# BYOB-BoosterPack-Template.net
KiCad netlist of a schematic drawn in EAGLE
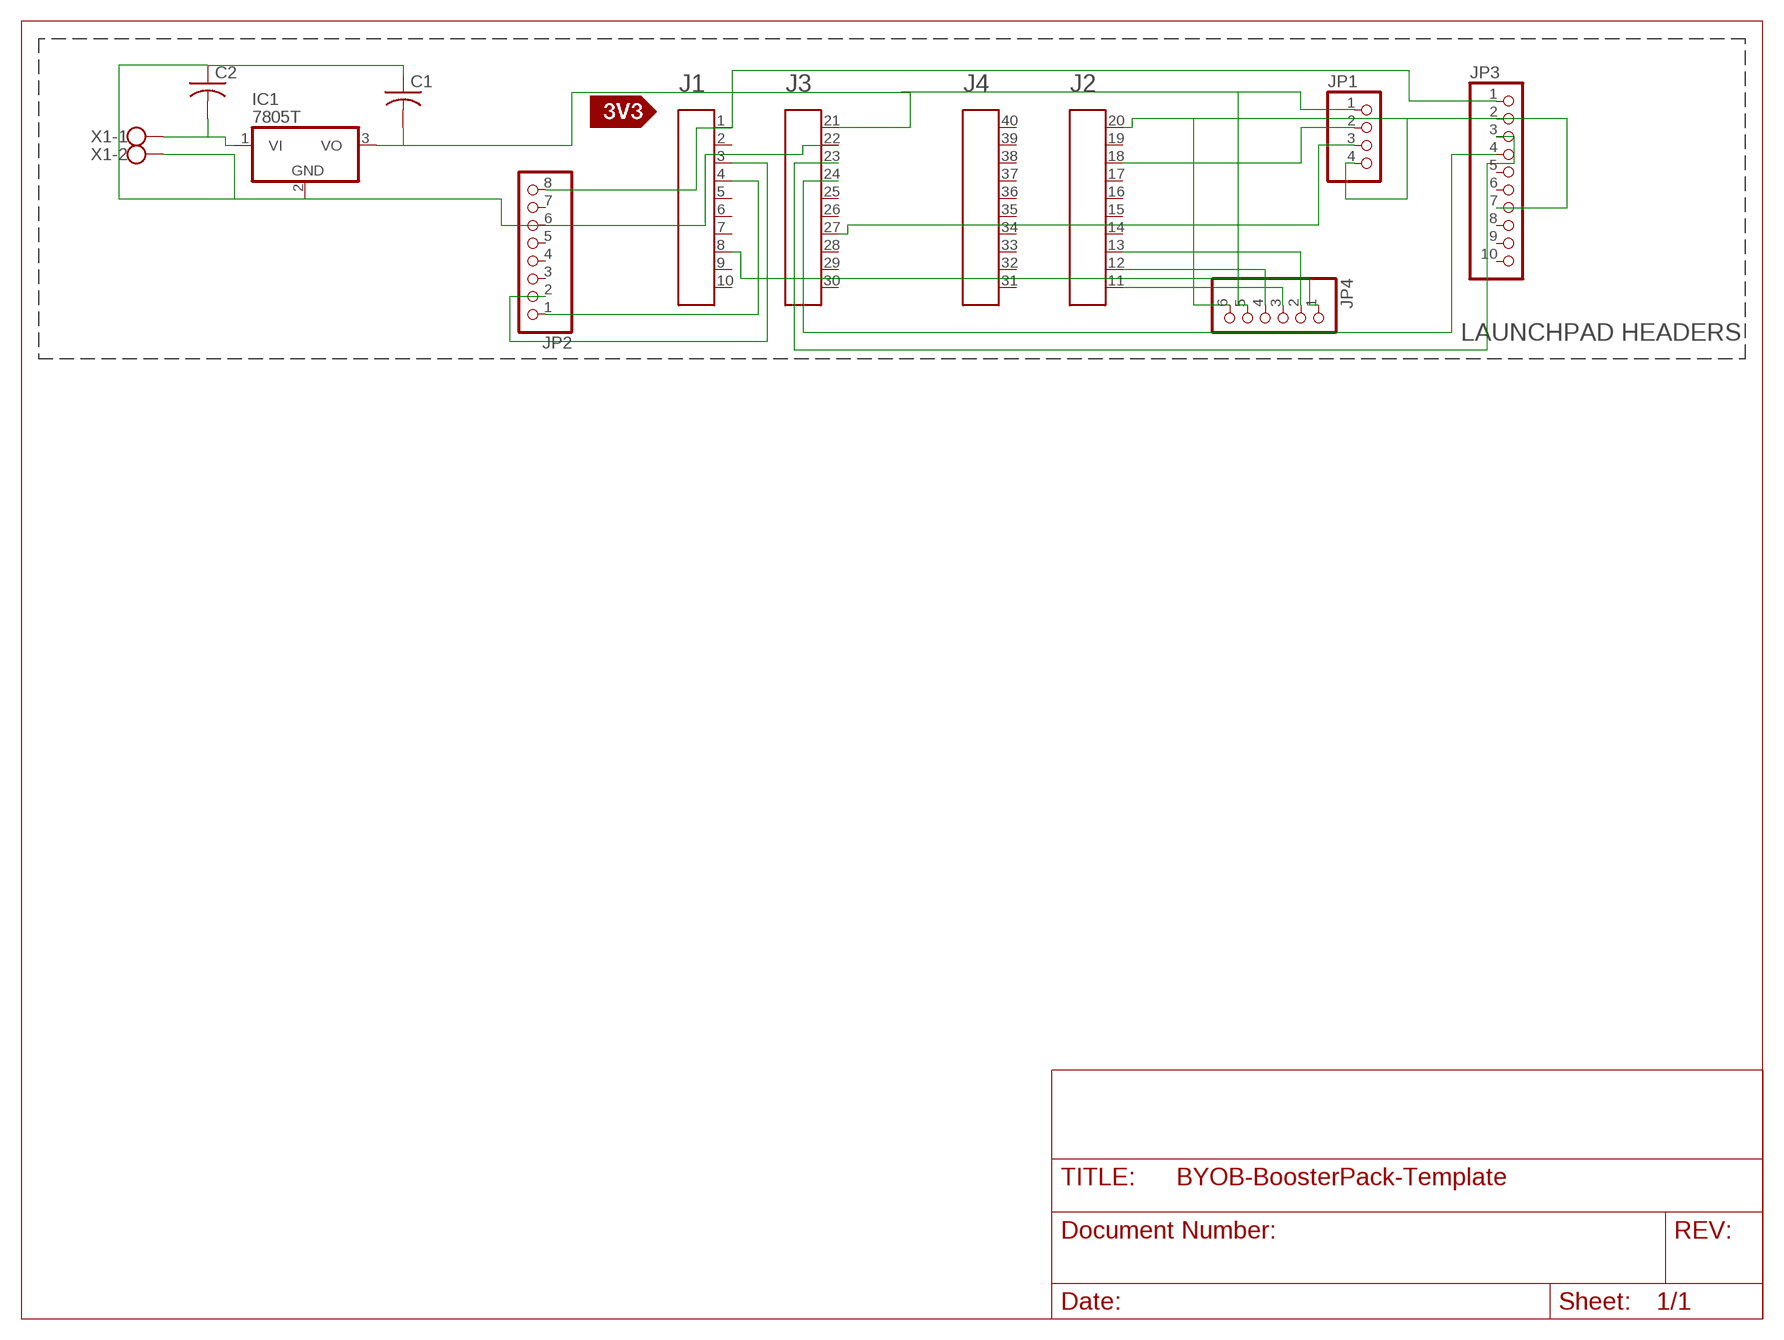
[diagram p0: schematic, sheet 1]

(export (version "E")
  (design (tool "Eeschema 10.0.6"))
  (components
    (comp (ref "A1")
      (value "HEADER4X10-BOOSTERPACK")
      (footprint "eagle-import:4X10-BOOSTERPACK")
      (libsource (lib "eagle-import") (part "HEADER4X10-BOOSTERPACK"))
    )
    (comp (ref "C1")
      (value "C-US025-025X050")
      (footprint "eagle-import:C025-025X050")
      (libsource (lib "eagle-import") (part "C-US025-025X050"))
    )
    (comp (ref "C2")
      (value "C-US025-025X050")
      (footprint "eagle-import:C025-025X050")
      (libsource (lib "eagle-import") (part "C-US025-025X050"))
    )
    (comp (ref "IC1")
      (value "7805T")
      (footprint "eagle-import:TO220H")
      (libsource (lib "eagle-import") (part "78T05"))
    )
    (comp (ref "JP1")
      (value "PINHD-1X4")
      (footprint "eagle-import:1X04")
      (libsource (lib "eagle-import") (part "PINHD-1X4"))
    )
    (comp (ref "JP2")
      (value "PINHD-1X8")
      (footprint "eagle-import:1X08")
      (libsource (lib "eagle-import") (part "PINHD-1X8"))
    )
    (comp (ref "JP3")
      (value "PINHD-1X10")
      (footprint "eagle-import:1X10")
      (libsource (lib "eagle-import") (part "PINHD-1X10"))
    )
    (comp (ref "JP4")
      (value "PINHD-1X6")
      (footprint "eagle-import:1X06")
      (libsource (lib "eagle-import") (part "PINHD-1X6"))
    )
    (comp (ref "U$3")
      (value "SILK_3V3_TAG")
      (footprint "eagle-import:SILK_3V3_TAG")
      (libsource (lib "eagle-import") (part "SILK_3V3_TAG"))
    )
    (comp (ref "X1")
      (value "W237-102")
      (footprint "eagle-import:W237-102")
      (fields (field (name "MPN") "237-102"))
      (libsource (lib "eagle-import") (part "W237-102"))
    )
  )
  (nets
    (net (code "1") (name "/GND") (class "Default")
      (node (ref "A1") (pin "20") (pinfunction "P$20_20") (pintype "bidirectional"))
      (node (ref "A1") (pin "22") (pinfunction "P$22_22") (pintype "bidirectional"))
      (node (ref "C1") (pin "1") (pinfunction "1_1") (pintype "passive"))
      (node (ref "C2") (pin "1") (pinfunction "1_1") (pintype "passive"))
      (node (ref "IC1") (pin "2") (pinfunction "GND_2") (pintype "passive"))
      (node (ref "JP1") (pin "4") (pinfunction "4_4") (pintype "passive"))
      (node (ref "JP2") (pin "6") (pinfunction "6_6") (pintype "passive"))
      (node (ref "JP3") (pin "2") (pinfunction "2_2") (pintype "passive"))
      (node (ref "JP3") (pin "7") (pinfunction "7_7") (pintype "passive"))
      (node (ref "JP4") (pin "6") (pinfunction "6_6") (pintype "passive"))
      (node (ref "X1") (pin "2") (pinfunction "KL_2") (pintype "passive"))
    )
    (net (code "2") (name "Net-(A1-P$1)") (class "Default")
      (node (ref "A1") (pin "1") (pinfunction "P$1_1") (pintype "bidirectional"))
      (node (ref "JP2") (pin "8") (pinfunction "8_8") (pintype "passive"))
      (node (ref "JP3") (pin "1") (pinfunction "1_1") (pintype "passive"))
    )
    (net (code "3") (name "Net-(A1-P$3)") (class "Default")
      (node (ref "A1") (pin "3") (pinfunction "P$3_3") (pintype "bidirectional"))
      (node (ref "JP2") (pin "2") (pinfunction "2_2") (pintype "passive"))
    )
    (net (code "4") (name "Net-(A1-P$4)") (class "Default")
      (node (ref "A1") (pin "4") (pinfunction "P$4_4") (pintype "bidirectional"))
      (node (ref "JP2") (pin "1") (pinfunction "1_1") (pintype "passive"))
    )
    (net (code "5") (name "Net-(A1-P$8)") (class "Default")
      (node (ref "A1") (pin "8") (pinfunction "P$8_8") (pintype "bidirectional"))
      (node (ref "JP4") (pin "1") (pinfunction "1_1") (pintype "passive"))
    )
    (net (code "6") (name "Net-(A1-P$11)") (class "Default")
      (node (ref "A1") (pin "11") (pinfunction "P$11_11") (pintype "bidirectional"))
      (node (ref "JP4") (pin "3") (pinfunction "3_3") (pintype "passive"))
    )
    (net (code "7") (name "Net-(A1-P$12)") (class "Default")
      (node (ref "A1") (pin "12") (pinfunction "P$12_12") (pintype "bidirectional"))
      (node (ref "JP4") (pin "4") (pinfunction "4_4") (pintype "passive"))
    )
    (net (code "8") (name "Net-(A1-P$13)") (class "Default")
      (node (ref "A1") (pin "13") (pinfunction "P$13_13") (pintype "bidirectional"))
      (node (ref "JP4") (pin "2") (pinfunction "2_2") (pintype "passive"))
    )
    (net (code "9") (name "Net-(A1-P$18)") (class "Default")
      (node (ref "A1") (pin "18") (pinfunction "P$18_18") (pintype "bidirectional"))
      (node (ref "JP1") (pin "2") (pinfunction "2_2") (pintype "passive"))
    )
    (net (code "10") (name "Net-(A1-P$21)") (class "Default")
      (node (ref "A1") (pin "21") (pinfunction "P$21_21") (pintype "bidirectional"))
      (node (ref "C1") (pin "2") (pinfunction "2_2") (pintype "passive"))
      (node (ref "IC1") (pin "3") (pinfunction "VO_3") (pintype "passive"))
      (node (ref "JP1") (pin "1") (pinfunction "1_1") (pintype "passive"))
      (node (ref "JP4") (pin "5") (pinfunction "5_5") (pintype "passive"))
    )
    (net (code "11") (name "Net-(A1-P$23)") (class "Default")
      (node (ref "A1") (pin "23") (pinfunction "P$23_23") (pintype "bidirectional"))
      (node (ref "JP3") (pin "3") (pinfunction "3_3") (pintype "passive"))
    )
    (net (code "12") (name "Net-(A1-P$24)") (class "Default")
      (node (ref "A1") (pin "24") (pinfunction "P$24_24") (pintype "bidirectional"))
      (node (ref "JP3") (pin "4") (pinfunction "4_4") (pintype "passive"))
    )
    (net (code "13") (name "Net-(A1-P$27)") (class "Default")
      (node (ref "A1") (pin "27") (pinfunction "P$27_27") (pintype "bidirectional"))
      (node (ref "JP1") (pin "3") (pinfunction "3_3") (pintype "passive"))
    )
    (net (code "14") (name "Net-(IC1-VI)") (class "Default")
      (node (ref "C2") (pin "2") (pinfunction "2_2") (pintype "passive"))
      (node (ref "IC1") (pin "1") (pinfunction "VI_1") (pintype "input"))
      (node (ref "X1") (pin "1") (pinfunction "KL_1") (pintype "passive"))
    )
    (net (code "15") (name "unconnected-(A1-P$2-Pad2)") (class "Default")
      (node (ref "A1") (pin "2") (pinfunction "P$2_2") (pintype "bidirectional"))
    )
    (net (code "16") (name "unconnected-(A1-P$5-Pad5)") (class "Default")
      (node (ref "A1") (pin "5") (pinfunction "P$5_5") (pintype "bidirectional"))
    )
    (net (code "17") (name "unconnected-(A1-P$6-Pad6)") (class "Default")
      (node (ref "A1") (pin "6") (pinfunction "P$6_6") (pintype "bidirectional"))
    )
    (net (code "18") (name "unconnected-(A1-P$7-Pad7)") (class "Default")
      (node (ref "A1") (pin "7") (pinfunction "P$7_7") (pintype "bidirectional"))
    )
    (net (code "19") (name "unconnected-(A1-P$9-Pad9)") (class "Default")
      (node (ref "A1") (pin "9") (pinfunction "P$9_9") (pintype "bidirectional"))
    )
    (net (code "20") (name "unconnected-(A1-P$10-Pad10)") (class "Default")
      (node (ref "A1") (pin "10") (pinfunction "P$10_10") (pintype "bidirectional"))
    )
    (net (code "21") (name "unconnected-(A1-P$14-Pad14)") (class "Default")
      (node (ref "A1") (pin "14") (pinfunction "P$14_14") (pintype "bidirectional"))
    )
    (net (code "22") (name "unconnected-(A1-P$15-Pad15)") (class "Default")
      (node (ref "A1") (pin "15") (pinfunction "P$15_15") (pintype "bidirectional"))
    )
    (net (code "23") (name "unconnected-(A1-P$16-Pad16)") (class "Default")
      (node (ref "A1") (pin "16") (pinfunction "P$16_16") (pintype "bidirectional"))
    )
    (net (code "24") (name "unconnected-(A1-P$17-Pad17)") (class "Default")
      (node (ref "A1") (pin "17") (pinfunction "P$17_17") (pintype "bidirectional"))
    )
    (net (code "25") (name "unconnected-(A1-P$19-Pad19)") (class "Default")
      (node (ref "A1") (pin "19") (pinfunction "P$19_19") (pintype "bidirectional"))
    )
    (net (code "26") (name "unconnected-(A1-P$25-Pad25)") (class "Default")
      (node (ref "A1") (pin "25") (pinfunction "P$25_25") (pintype "bidirectional"))
    )
    (net (code "27") (name "unconnected-(A1-P$26-Pad26)") (class "Default")
      (node (ref "A1") (pin "26") (pinfunction "P$26_26") (pintype "bidirectional"))
    )
    (net (code "28") (name "unconnected-(A1-P$28-Pad28)") (class "Default")
      (node (ref "A1") (pin "28") (pinfunction "P$28_28") (pintype "bidirectional"))
    )
    (net (code "29") (name "unconnected-(A1-P$29-Pad29)") (class "Default")
      (node (ref "A1") (pin "29") (pinfunction "P$29_29") (pintype "bidirectional"))
    )
    (net (code "30") (name "unconnected-(A1-P$30-Pad30)") (class "Default")
      (node (ref "A1") (pin "30") (pinfunction "P$30_30") (pintype "bidirectional"))
    )
    (net (code "31") (name "unconnected-(A1-P$31-Pad31)") (class "Default")
      (node (ref "A1") (pin "31") (pinfunction "P$31_31") (pintype "bidirectional"))
    )
    (net (code "32") (name "unconnected-(A1-P$32-Pad32)") (class "Default")
      (node (ref "A1") (pin "32") (pinfunction "P$32_32") (pintype "bidirectional"))
    )
    (net (code "33") (name "unconnected-(A1-P$33-Pad33)") (class "Default")
      (node (ref "A1") (pin "33") (pinfunction "P$33_33") (pintype "bidirectional"))
    )
    (net (code "34") (name "unconnected-(A1-P$34-Pad34)") (class "Default")
      (node (ref "A1") (pin "34") (pinfunction "P$34_34") (pintype "bidirectional"))
    )
    (net (code "35") (name "unconnected-(A1-P$35-Pad35)") (class "Default")
      (node (ref "A1") (pin "35") (pinfunction "P$35_35") (pintype "bidirectional"))
    )
    (net (code "36") (name "unconnected-(A1-P$36-Pad36)") (class "Default")
      (node (ref "A1") (pin "36") (pinfunction "P$36_36") (pintype "bidirectional"))
    )
    (net (code "37") (name "unconnected-(A1-P$37-Pad37)") (class "Default")
      (node (ref "A1") (pin "37") (pinfunction "P$37_37") (pintype "bidirectional"))
    )
    (net (code "38") (name "unconnected-(A1-P$38-Pad38)") (class "Default")
      (node (ref "A1") (pin "38") (pinfunction "P$38_38") (pintype "bidirectional"))
    )
    (net (code "39") (name "unconnected-(A1-P$39-Pad39)") (class "Default")
      (node (ref "A1") (pin "39") (pinfunction "P$39_39") (pintype "bidirectional"))
    )
    (net (code "40") (name "unconnected-(A1-P$40-Pad40)") (class "Default")
      (node (ref "A1") (pin "40") (pinfunction "P$40_40") (pintype "bidirectional"))
    )
    (net (code "41") (name "unconnected-(JP2-Pad3)") (class "Default")
      (node (ref "JP2") (pin "3") (pinfunction "3_3") (pintype "passive"))
    )
    (net (code "42") (name "unconnected-(JP2-Pad4)") (class "Default")
      (node (ref "JP2") (pin "4") (pinfunction "4_4") (pintype "passive"))
    )
    (net (code "43") (name "unconnected-(JP2-Pad5)") (class "Default")
      (node (ref "JP2") (pin "5") (pinfunction "5_5") (pintype "passive"))
    )
    (net (code "44") (name "unconnected-(JP2-Pad7)") (class "Default")
      (node (ref "JP2") (pin "7") (pinfunction "7_7") (pintype "passive"))
    )
    (net (code "45") (name "unconnected-(JP3-Pad5)") (class "Default")
      (node (ref "JP3") (pin "5") (pinfunction "5_5") (pintype "passive"))
    )
    (net (code "46") (name "unconnected-(JP3-Pad6)") (class "Default")
      (node (ref "JP3") (pin "6") (pinfunction "6_6") (pintype "passive"))
    )
    (net (code "47") (name "unconnected-(JP3-Pad8)") (class "Default")
      (node (ref "JP3") (pin "8") (pinfunction "8_8") (pintype "passive"))
    )
    (net (code "48") (name "unconnected-(JP3-Pad9)") (class "Default")
      (node (ref "JP3") (pin "9") (pinfunction "9_9") (pintype "passive"))
    )
    (net (code "49") (name "unconnected-(JP3-Pad10)") (class "Default")
      (node (ref "JP3") (pin "10") (pinfunction "10_10") (pintype "passive"))
    )
  )
)
